# BW1097_AV.net
KiCad netlist of a schematic drawn in Altium Designer
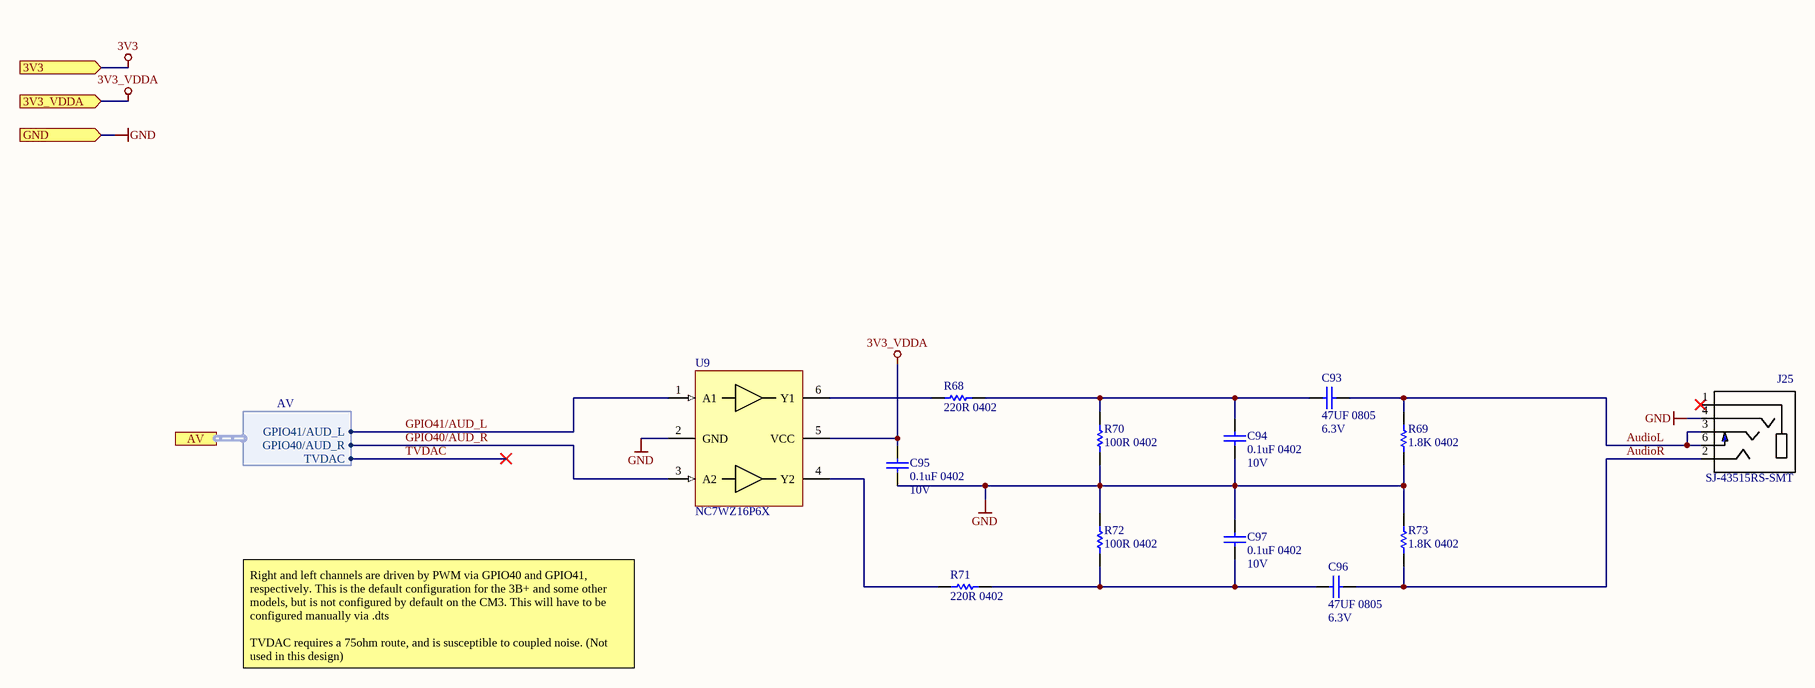
[diagram p0: BW1097_AV.SchDoc]

(export (version "E")
  (design (tool "Eeschema 10.0.6"))
  (components
    (comp (ref "C93")
      (value "47UF 0805")
      (footprint "CAP_Altium_Vault_Generic:CAPC0805(2012)145_N")
      (description "CAP CER 47UF 6.3V X5R 0805")
      (fields (field (name "TOLERANCE") "20%") (field (name "VOLTAGE") "6.3V"))
      (libsource (lib "LuxonisMaster") (part "GRM21BR60J476ME15L"))
    )
    (comp (ref "C94")
      (value "0.1uF 0402")
      (footprint "CAP_Altium_Vault_Generic:CAPC0402(1005)70_N")
      (description "CAP CER 0.1UF 10V X7R 0402 5%")
      (fields (field (name "TOLERANCE") "5%") (field (name "VOLTAGE RATING") "10V"))
      (libsource (lib "LuxonisMaster") (part "GRM155R71A104JA01D"))
    )
    (comp (ref "C95")
      (value "0.1uF 0402")
      (footprint "CAP_Altium_Vault_Generic:CAPC0402(1005)70_N")
      (description "CAP CER 0.1UF 10V X7R 0402 5%")
      (fields (field (name "TOLERANCE") "5%") (field (name "VOLTAGE RATING") "10V"))
      (libsource (lib "LuxonisMaster") (part "GRM155R71A104JA01D"))
    )
    (comp (ref "C96")
      (value "47UF 0805")
      (footprint "CAP_Altium_Vault_Generic:CAPC0805(2012)145_N")
      (description "CAP CER 47UF 6.3V X5R 0805")
      (fields (field (name "TOLERANCE") "20%") (field (name "VOLTAGE") "6.3V"))
      (libsource (lib "LuxonisMaster") (part "GRM21BR60J476ME15L"))
    )
    (comp (ref "C97")
      (value "0.1uF 0402")
      (footprint "CAP_Altium_Vault_Generic:CAPC0402(1005)70_N")
      (description "CAP CER 0.1UF 10V X7R 0402 5%")
      (fields (field (name "TOLERANCE") "5%") (field (name "VOLTAGE RATING") "10V"))
      (libsource (lib "LuxonisMaster") (part "GRM155R71A104JA01D"))
    )
    (comp (ref "J25")
      (value "SJ-43515RS-SMT")
      (footprint "LuxonisMaster:SJ-43515RS-SMT")
      (description "CONN JACK 4COND 3.5MM SMD R/A")
      (libsource (lib "LuxonisMaster") (part "SJ-43515RS-SMT"))
    )
    (comp (ref "R68")
      (value "220R 0402")
      (footprint "RES_Altium_Vault_Generic:RESC0402(1005)_N")
      (description "RES SMD 220 OHM 1% 1/16W 0402")
      (fields (field (name "TOLERANCE") "1%"))
      (libsource (lib "LuxonisMaster") (part "RC0402FR-07220RL"))
    )
    (comp (ref "R69")
      (value "1.8K 0402")
      (footprint "RES_Altium_Vault_Generic:RESC0402(1005)_N")
      (description "RES SMD 1.8K OHM 1% 1/16W 0402")
      (fields (field (name "TOLERANCE") "1%"))
      (libsource (lib "LuxonisMaster") (part "RC0402FR-071K8L"))
    )
    (comp (ref "R70")
      (value "100R 0402")
      (footprint "RES_Altium_Vault_Generic:RESC0402(1005)_N")
      (description "RES SMD 100 OHM 1% 1/16W 0402")
      (fields (field (name "TOLERANCE") "1%"))
      (libsource (lib "LuxonisMaster") (part "RC0402FR-07100RL"))
    )
    (comp (ref "R71")
      (value "220R 0402")
      (footprint "RES_Altium_Vault_Generic:RESC0402(1005)_N")
      (description "RES SMD 220 OHM 1% 1/16W 0402")
      (fields (field (name "TOLERANCE") "1%"))
      (libsource (lib "LuxonisMaster") (part "RC0402FR-07220RL"))
    )
    (comp (ref "R72")
      (value "100R 0402")
      (footprint "RES_Altium_Vault_Generic:RESC0402(1005)_N")
      (description "RES SMD 100 OHM 1% 1/16W 0402")
      (fields (field (name "TOLERANCE") "1%"))
      (libsource (lib "LuxonisMaster") (part "RC0402FR-07100RL"))
    )
    (comp (ref "R73")
      (value "1.8K 0402")
      (footprint "RES_Altium_Vault_Generic:RESC0402(1005)_N")
      (description "RES SMD 1.8K OHM 1% 1/16W 0402")
      (fields (field (name "TOLERANCE") "1%"))
      (libsource (lib "LuxonisMaster") (part "RC0402FR-071K8L"))
    )
    (comp (ref "U9")
      (value "NC7WZ16P6X")
      (footprint "LuxonisMaster:NC7WZ16P6X")
      (libsource (lib "LuxonisMaster") (part "NC7WZ16P6X"))
    )
  )
  (nets
    (net (code "2") (name "/AudioL") (class "Default")
      (node (ref "C93") (pin "1") (pinfunction "1_1") (pintype "passive"))
      (node (ref "J25") (pin "3") (pinfunction "RING1_3") (pintype "passive"))
      (node (ref "J25") (pin "6") (pinfunction "RING_SWITCH_6") (pintype "passive"))
      (node (ref "R69") (pin "2") (pinfunction "2_2") (pintype "passive"))
    )
    (net (code "3") (name "/AudioR") (class "Default")
      (node (ref "C96") (pin "1") (pinfunction "1_1") (pintype "passive"))
      (node (ref "J25") (pin "2") (pinfunction "TIP_2") (pintype "passive"))
      (node (ref "R73") (pin "2") (pinfunction "2_2") (pintype "passive"))
    )
    (net (code "4") (name "/GPIO40{slash}AUD_R") (class "Default")
      (node (ref "U9") (pin "3") (pinfunction "A2_3") (pintype "input"))
    )
    (net (code "5") (name "/GPIO41{slash}AUD_L") (class "Default")
      (node (ref "U9") (pin "1") (pinfunction "A1_1") (pintype "input"))
    )
    (net (code "9") (name "3V3_VDDA") (class "Default")
      (node (ref "C95") (pin "2") (pinfunction "2_2") (pintype "passive"))
      (node (ref "U9") (pin "5") (pinfunction "VCC_5") (pintype "power_in"))
    )
    (net (code "10") (name "GND") (class "Default")
      (node (ref "C94") (pin "1") (pinfunction "1_1") (pintype "passive"))
      (node (ref "C95") (pin "1") (pinfunction "1_1") (pintype "passive"))
      (node (ref "C97") (pin "1") (pinfunction "1_1") (pintype "passive"))
      (node (ref "J25") (pin "4") (pinfunction "RING2_4") (pintype "passive"))
      (node (ref "R69") (pin "1") (pinfunction "1_1") (pintype "passive"))
      (node (ref "R70") (pin "1") (pinfunction "1_1") (pintype "passive"))
      (node (ref "R72") (pin "1") (pinfunction "1_1") (pintype "passive"))
      (node (ref "R73") (pin "1") (pinfunction "1_1") (pintype "passive"))
      (node (ref "U9") (pin "2") (pinfunction "GND_2") (pintype "power_in"))
    )
    (net (code "11") (name "Net-(C93-Pad2)") (class "Default")
      (node (ref "C93") (pin "2") (pinfunction "2_2") (pintype "passive"))
      (node (ref "C94") (pin "2") (pinfunction "2_2") (pintype "passive"))
      (node (ref "R68") (pin "2") (pinfunction "2_2") (pintype "passive"))
      (node (ref "R70") (pin "2") (pinfunction "2_2") (pintype "passive"))
    )
    (net (code "12") (name "Net-(C96-Pad2)") (class "Default")
      (node (ref "C96") (pin "2") (pinfunction "2_2") (pintype "passive"))
      (node (ref "C97") (pin "2") (pinfunction "2_2") (pintype "passive"))
      (node (ref "R71") (pin "2") (pinfunction "2_2") (pintype "passive"))
      (node (ref "R72") (pin "2") (pinfunction "2_2") (pintype "passive"))
    )
    (net (code "13") (name "Net-(U9-Y1)") (class "Default")
      (node (ref "R68") (pin "1") (pinfunction "1_1") (pintype "passive"))
      (node (ref "U9") (pin "6") (pinfunction "Y1_6") (pintype "open_collector"))
    )
    (net (code "14") (name "Net-(U9-Y2)") (class "Default")
      (node (ref "R71") (pin "1") (pinfunction "1_1") (pintype "passive"))
      (node (ref "U9") (pin "4") (pinfunction "Y2_4") (pintype "open_collector"))
    )
    (net (code "15") (name "unconnected-(J25-SLEEVE-Pad1)") (class "Default")
      (node (ref "J25") (pin "1") (pinfunction "SLEEVE_1") (pintype "passive+no_connect"))
    )
  )
)
